# io3.net
KiCad netlist of a schematic drawn in EAGLE
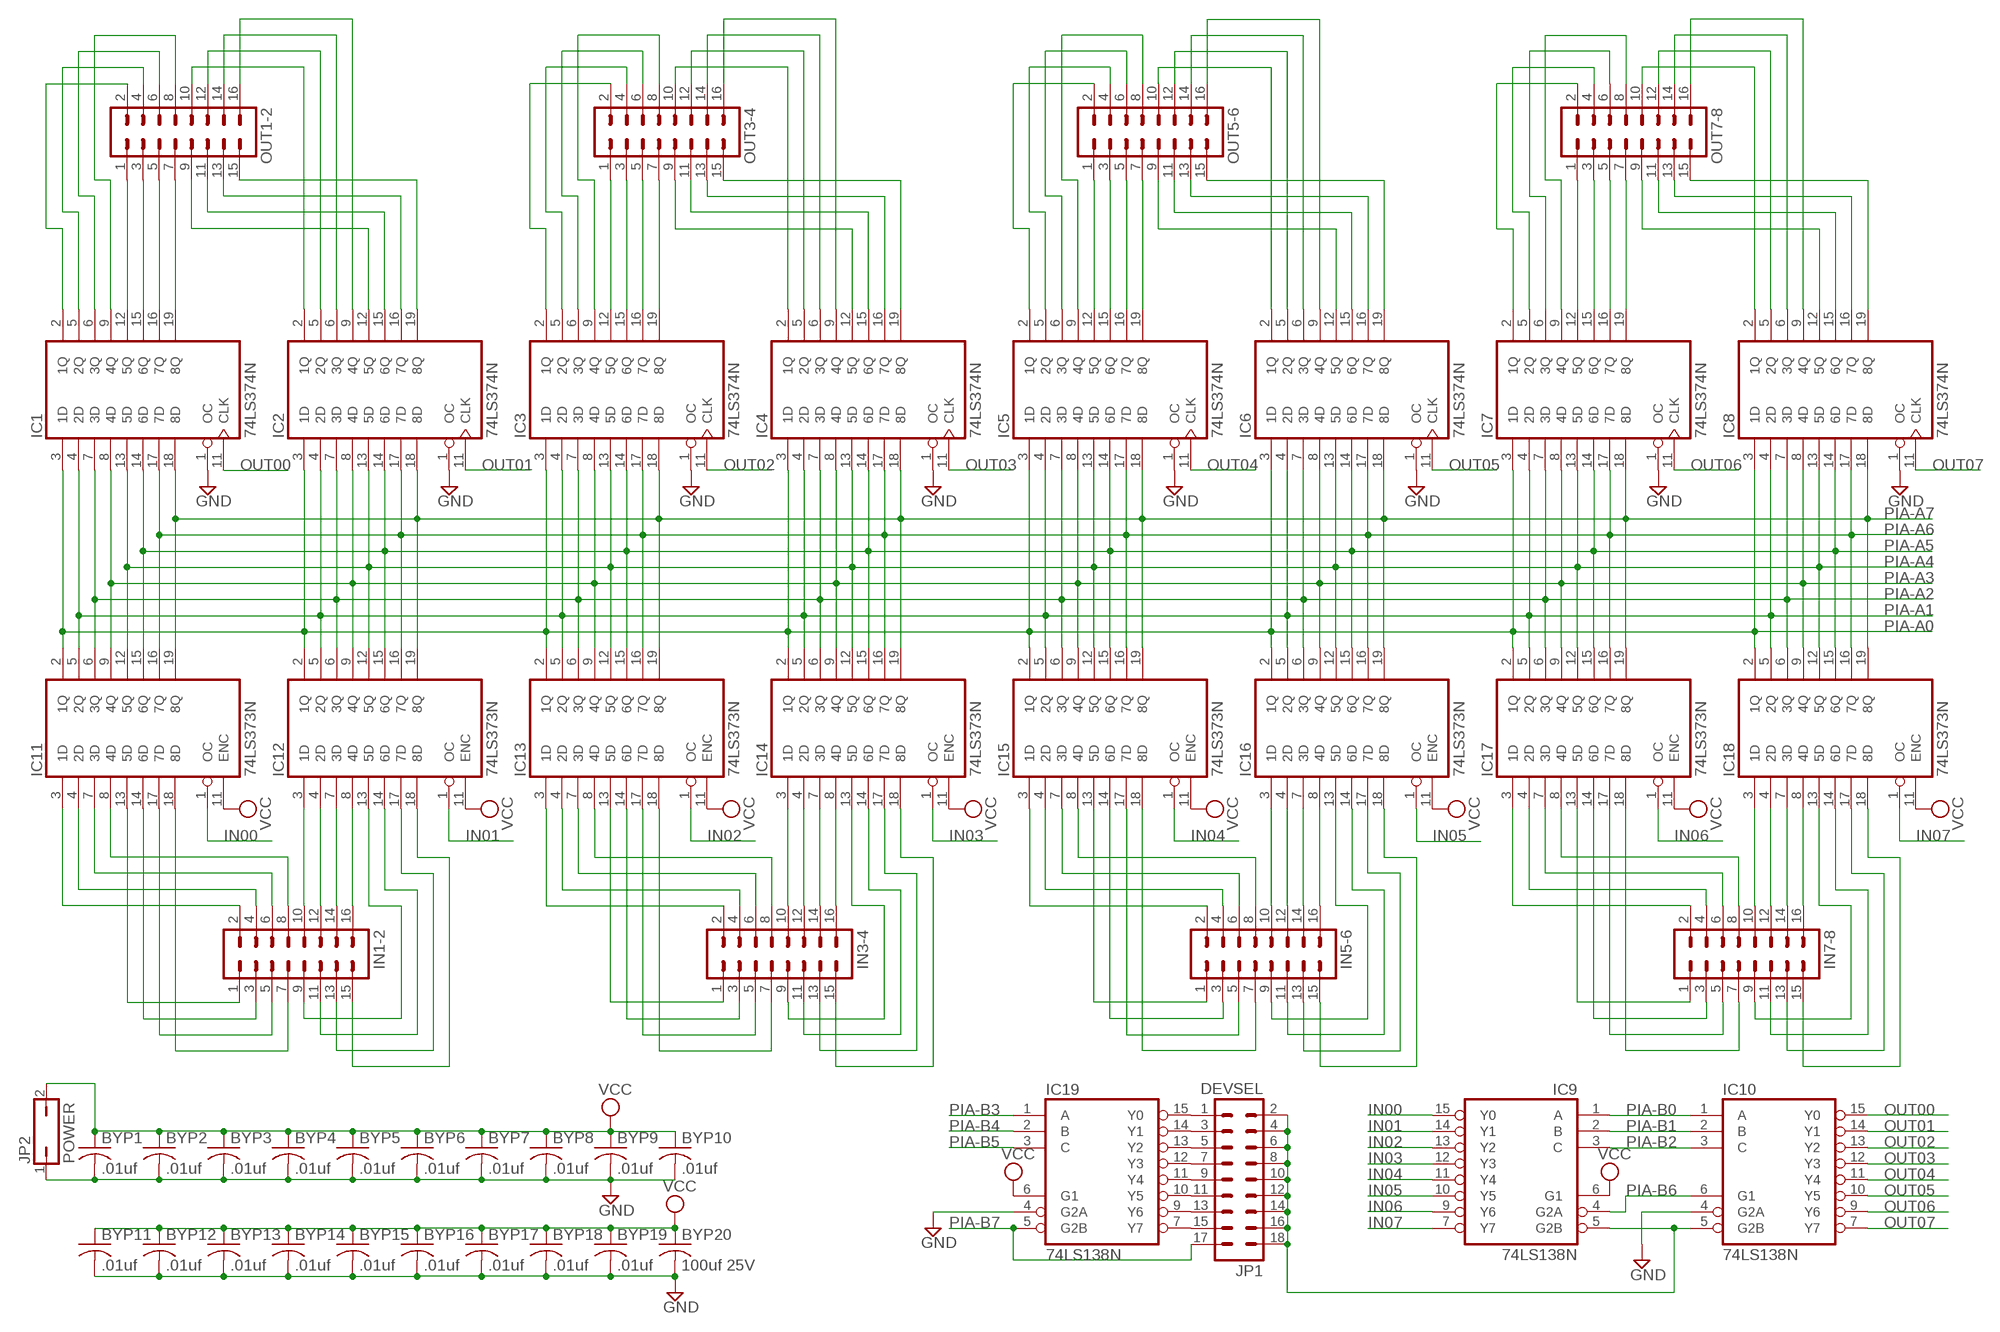
[diagram p0: schematic, sheet 1]
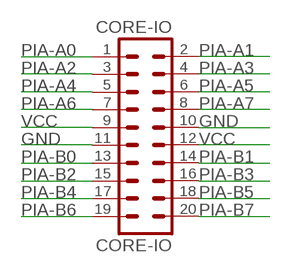
[diagram p1: schematic, sheet 2]

(export (version "E")
  (design (tool "Eeschema 10.0.6"))
  (components
    (comp (ref "CORE-IO")
      (value "CORE-IO")
      (footprint "eagle-import:MA10-2")
      (libsource (lib "eagle-import") (part "MA10-2"))
    )
    (comp (ref "BYP1")
      (value ".01uf")
      (footprint "eagle-import:C050-025X075")
      (libsource (lib "eagle-import") (part "C-US050-025X075"))
    )
    (comp (ref "BYP2")
      (value ".01uf")
      (footprint "eagle-import:C050-025X075")
      (libsource (lib "eagle-import") (part "C-US050-025X075"))
    )
    (comp (ref "BYP3")
      (value ".01uf")
      (footprint "eagle-import:C050-025X075")
      (libsource (lib "eagle-import") (part "C-US050-025X075"))
    )
    (comp (ref "BYP4")
      (value ".01uf")
      (footprint "eagle-import:C050-025X075")
      (libsource (lib "eagle-import") (part "C-US050-025X075"))
    )
    (comp (ref "BYP5")
      (value ".01uf")
      (footprint "eagle-import:C050-025X075")
      (libsource (lib "eagle-import") (part "C-US050-025X075"))
    )
    (comp (ref "BYP6")
      (value ".01uf")
      (footprint "eagle-import:C050-025X075")
      (libsource (lib "eagle-import") (part "C-US050-025X075"))
    )
    (comp (ref "BYP7")
      (value ".01uf")
      (footprint "eagle-import:C050-025X075")
      (libsource (lib "eagle-import") (part "C-US050-025X075"))
    )
    (comp (ref "BYP8")
      (value ".01uf")
      (footprint "eagle-import:C050-025X075")
      (libsource (lib "eagle-import") (part "C-US050-025X075"))
    )
    (comp (ref "BYP9")
      (value ".01uf")
      (footprint "eagle-import:C050-025X075")
      (libsource (lib "eagle-import") (part "C-US050-025X075"))
    )
    (comp (ref "BYP10")
      (value ".01uf")
      (footprint "eagle-import:C050-025X075")
      (libsource (lib "eagle-import") (part "C-US050-025X075"))
    )
    (comp (ref "BYP11")
      (value ".01uf")
      (footprint "eagle-import:C050-025X075")
      (libsource (lib "eagle-import") (part "C-US050-025X075"))
    )
    (comp (ref "BYP12")
      (value ".01uf")
      (footprint "eagle-import:C050-025X075")
      (libsource (lib "eagle-import") (part "C-US050-025X075"))
    )
    (comp (ref "BYP13")
      (value ".01uf")
      (footprint "eagle-import:C050-025X075")
      (libsource (lib "eagle-import") (part "C-US050-025X075"))
    )
    (comp (ref "BYP14")
      (value ".01uf")
      (footprint "eagle-import:C050-025X075")
      (libsource (lib "eagle-import") (part "C-US050-025X075"))
    )
    (comp (ref "BYP15")
      (value ".01uf")
      (footprint "eagle-import:C050-025X075")
      (libsource (lib "eagle-import") (part "C-US050-025X075"))
    )
    (comp (ref "BYP16")
      (value ".01uf")
      (footprint "eagle-import:C050-025X075")
      (libsource (lib "eagle-import") (part "C-US050-025X075"))
    )
    (comp (ref "BYP17")
      (value ".01uf")
      (footprint "eagle-import:C050-025X075")
      (libsource (lib "eagle-import") (part "C-US050-025X075"))
    )
    (comp (ref "BYP18")
      (value ".01uf")
      (footprint "eagle-import:C050-025X075")
      (libsource (lib "eagle-import") (part "C-US050-025X075"))
    )
    (comp (ref "BYP19")
      (value ".01uf")
      (footprint "eagle-import:C050-025X075")
      (libsource (lib "eagle-import") (part "C-US050-025X075"))
    )
    (comp (ref "BYP20")
      (value "100uf 25V")
      (footprint "eagle-import:C150-064X183")
      (libsource (lib "eagle-import") (part "C-US150-064X183"))
    )
    (comp (ref "IC1")
      (value "74LS374N")
      (footprint "eagle-import:DIL20")
      (libsource (lib "eagle-import") (part "74374NLS"))
    )
    (comp (ref "IC2")
      (value "74LS374N")
      (footprint "eagle-import:DIL20")
      (libsource (lib "eagle-import") (part "74374NLS"))
    )
    (comp (ref "IC3")
      (value "74LS374N")
      (footprint "eagle-import:DIL20")
      (libsource (lib "eagle-import") (part "74374NLS"))
    )
    (comp (ref "IC4")
      (value "74LS374N")
      (footprint "eagle-import:DIL20")
      (libsource (lib "eagle-import") (part "74374NLS"))
    )
    (comp (ref "IC5")
      (value "74LS374N")
      (footprint "eagle-import:DIL20")
      (libsource (lib "eagle-import") (part "74374NLS"))
    )
    (comp (ref "IC6")
      (value "74LS374N")
      (footprint "eagle-import:DIL20")
      (libsource (lib "eagle-import") (part "74374NLS"))
    )
    (comp (ref "IC7")
      (value "74LS374N")
      (footprint "eagle-import:DIL20")
      (libsource (lib "eagle-import") (part "74374NLS"))
    )
    (comp (ref "IC8")
      (value "74LS374N")
      (footprint "eagle-import:DIL20")
      (libsource (lib "eagle-import") (part "74374NLS"))
    )
    (comp (ref "IC9")
      (value "74LS138N")
      (footprint "eagle-import:DIL16")
      (libsource (lib "eagle-import") (part "74138NLS"))
    )
    (comp (ref "IC10")
      (value "74LS138N")
      (footprint "eagle-import:DIL16")
      (libsource (lib "eagle-import") (part "74138NLS"))
    )
    (comp (ref "IC11")
      (value "74LS373N")
      (footprint "eagle-import:DIL20")
      (libsource (lib "eagle-import") (part "74373NLS"))
    )
    (comp (ref "IC12")
      (value "74LS373N")
      (footprint "eagle-import:DIL20")
      (libsource (lib "eagle-import") (part "74373NLS"))
    )
    (comp (ref "IC13")
      (value "74LS373N")
      (footprint "eagle-import:DIL20")
      (libsource (lib "eagle-import") (part "74373NLS"))
    )
    (comp (ref "IC14")
      (value "74LS373N")
      (footprint "eagle-import:DIL20")
      (libsource (lib "eagle-import") (part "74373NLS"))
    )
    (comp (ref "IC15")
      (value "74LS373N")
      (footprint "eagle-import:DIL20")
      (libsource (lib "eagle-import") (part "74373NLS"))
    )
    (comp (ref "IC16")
      (value "74LS373N")
      (footprint "eagle-import:DIL20")
      (libsource (lib "eagle-import") (part "74373NLS"))
    )
    (comp (ref "IC17")
      (value "74LS373N")
      (footprint "eagle-import:DIL20")
      (libsource (lib "eagle-import") (part "74373NLS"))
    )
    (comp (ref "IC18")
      (value "74LS373N")
      (footprint "eagle-import:DIL20")
      (libsource (lib "eagle-import") (part "74373NLS"))
    )
    (comp (ref "IC19")
      (value "74LS138N")
      (footprint "eagle-import:DIL16")
      (libsource (lib "eagle-import") (part "74138NLS"))
    )
    (comp (ref "IN1-2")
      (value "MA08-2")
      (footprint "eagle-import:MA08-2")
      (libsource (lib "eagle-import") (part "MA08-2"))
    )
    (comp (ref "IN3-4")
      (value "MA08-2")
      (footprint "eagle-import:MA08-2")
      (libsource (lib "eagle-import") (part "MA08-2"))
    )
    (comp (ref "IN5-6")
      (value "MA08-2")
      (footprint "eagle-import:MA08-2")
      (libsource (lib "eagle-import") (part "MA08-2"))
    )
    (comp (ref "IN7-8")
      (value "MA08-2")
      (footprint "eagle-import:MA08-2")
      (libsource (lib "eagle-import") (part "MA08-2"))
    )
    (comp (ref "JP1")
      (value "DEVSEL")
      (footprint "eagle-import:MA09-2")
      (libsource (lib "eagle-import") (part "MA09-2"))
    )
    (comp (ref "JP2")
      (value "POWER")
      (footprint "eagle-import:JP1")
      (libsource (lib "eagle-import") (part "JP1Q"))
    )
    (comp (ref "OUT1-2")
      (value "MA08-2")
      (footprint "eagle-import:MA08-2")
      (libsource (lib "eagle-import") (part "MA08-2"))
    )
    (comp (ref "OUT3-4")
      (value "MA08-2")
      (footprint "eagle-import:MA08-2")
      (libsource (lib "eagle-import") (part "MA08-2"))
    )
    (comp (ref "OUT5-6")
      (value "MA08-2")
      (footprint "eagle-import:MA08-2")
      (libsource (lib "eagle-import") (part "MA08-2"))
    )
    (comp (ref "OUT7-8")
      (value "MA08-2")
      (footprint "eagle-import:MA08-2")
      (libsource (lib "eagle-import") (part "MA08-2"))
    )
  )
  (nets
    (net (code "1") (name "GND") (class "Default")
      (node (ref "BYP1") (pin "2") (pinfunction "2_2") (pintype "passive"))
      (node (ref "BYP10") (pin "2") (pinfunction "2_2") (pintype "passive"))
      (node (ref "BYP11") (pin "2") (pinfunction "2_2") (pintype "passive"))
      (node (ref "BYP12") (pin "2") (pinfunction "2_2") (pintype "passive"))
      (node (ref "BYP13") (pin "2") (pinfunction "2_2") (pintype "passive"))
      (node (ref "BYP14") (pin "2") (pinfunction "2_2") (pintype "passive"))
      (node (ref "BYP15") (pin "2") (pinfunction "2_2") (pintype "passive"))
      (node (ref "BYP16") (pin "2") (pinfunction "2_2") (pintype "passive"))
      (node (ref "BYP17") (pin "2") (pinfunction "2_2") (pintype "passive"))
      (node (ref "BYP18") (pin "2") (pinfunction "2_2") (pintype "passive"))
      (node (ref "BYP19") (pin "2") (pinfunction "2_2") (pintype "passive"))
      (node (ref "BYP2") (pin "2") (pinfunction "2_2") (pintype "passive"))
      (node (ref "BYP20") (pin "2") (pinfunction "2_2") (pintype "passive"))
      (node (ref "BYP3") (pin "2") (pinfunction "2_2") (pintype "passive"))
      (node (ref "BYP4") (pin "2") (pinfunction "2_2") (pintype "passive"))
      (node (ref "BYP5") (pin "2") (pinfunction "2_2") (pintype "passive"))
      (node (ref "BYP6") (pin "2") (pinfunction "2_2") (pintype "passive"))
      (node (ref "BYP7") (pin "2") (pinfunction "2_2") (pintype "passive"))
      (node (ref "BYP8") (pin "2") (pinfunction "2_2") (pintype "passive"))
      (node (ref "BYP9") (pin "2") (pinfunction "2_2") (pintype "passive"))
      (node (ref "CORE-IO") (pin "10") (pinfunction "10_10") (pintype "passive"))
      (node (ref "CORE-IO") (pin "11") (pinfunction "11_11") (pintype "passive"))
      (node (ref "IC1") (pin "1") (pinfunction "OC_1") (pintype "input"))
      (node (ref "IC10") (pin "4") (pinfunction "G2A_4") (pintype "input"))
      (node (ref "IC19") (pin "4") (pinfunction "G2A_4") (pintype "input"))
      (node (ref "IC2") (pin "1") (pinfunction "OC_1") (pintype "input"))
      (node (ref "IC3") (pin "1") (pinfunction "OC_1") (pintype "input"))
      (node (ref "IC4") (pin "1") (pinfunction "OC_1") (pintype "input"))
      (node (ref "IC5") (pin "1") (pinfunction "OC_1") (pintype "input"))
      (node (ref "IC6") (pin "1") (pinfunction "OC_1") (pintype "input"))
      (node (ref "IC7") (pin "1") (pinfunction "OC_1") (pintype "input"))
      (node (ref "IC8") (pin "1") (pinfunction "OC_1") (pintype "input"))
      (node (ref "JP2") (pin "1") (pinfunction "1_1") (pintype "passive"))
    )
    (net (code "2") (name "IN00") (class "Default")
      (node (ref "IC11") (pin "1") (pinfunction "OC_1") (pintype "input"))
      (node (ref "IC9") (pin "15") (pinfunction "Y0_15") (pintype "output"))
    )
    (net (code "3") (name "IN01") (class "Default")
      (node (ref "IC12") (pin "1") (pinfunction "OC_1") (pintype "input"))
      (node (ref "IC9") (pin "14") (pinfunction "Y1_14") (pintype "output"))
    )
    (net (code "4") (name "IN02") (class "Default")
      (node (ref "IC13") (pin "1") (pinfunction "OC_1") (pintype "input"))
      (node (ref "IC9") (pin "13") (pinfunction "Y2_13") (pintype "output"))
    )
    (net (code "5") (name "IN03") (class "Default")
      (node (ref "IC14") (pin "1") (pinfunction "OC_1") (pintype "input"))
      (node (ref "IC9") (pin "12") (pinfunction "Y3_12") (pintype "output"))
    )
    (net (code "6") (name "IN04") (class "Default")
      (node (ref "IC15") (pin "1") (pinfunction "OC_1") (pintype "input"))
      (node (ref "IC9") (pin "11") (pinfunction "Y4_11") (pintype "output"))
    )
    (net (code "7") (name "IN05") (class "Default")
      (node (ref "IC16") (pin "1") (pinfunction "OC_1") (pintype "input"))
      (node (ref "IC9") (pin "10") (pinfunction "Y5_10") (pintype "output"))
    )
    (net (code "8") (name "IN06") (class "Default")
      (node (ref "IC17") (pin "1") (pinfunction "OC_1") (pintype "input"))
      (node (ref "IC9") (pin "9") (pinfunction "Y6_9") (pintype "output"))
    )
    (net (code "9") (name "IN07") (class "Default")
      (node (ref "IC18") (pin "1") (pinfunction "OC_1") (pintype "input"))
      (node (ref "IC9") (pin "7") (pinfunction "Y7_7") (pintype "output"))
    )
    (net (code "10") (name "Net-(IC1A-1Q)") (class "Default")
      (node (ref "IC1") (pin "2") (pinfunction "1Q_2") (pintype "tri_state"))
      (node (ref "OUT1-2") (pin "2") (pinfunction "2_2") (pintype "passive"))
    )
    (net (code "11") (name "Net-(IC1A-2Q)") (class "Default")
      (node (ref "IC1") (pin "5") (pinfunction "2Q_5") (pintype "tri_state"))
      (node (ref "OUT1-2") (pin "4") (pinfunction "4_4") (pintype "passive"))
    )
    (net (code "12") (name "Net-(IC1A-3Q)") (class "Default")
      (node (ref "IC1") (pin "6") (pinfunction "3Q_6") (pintype "tri_state"))
      (node (ref "OUT1-2") (pin "6") (pinfunction "6_6") (pintype "passive"))
    )
    (net (code "13") (name "Net-(IC1A-4Q)") (class "Default")
      (node (ref "IC1") (pin "9") (pinfunction "4Q_9") (pintype "tri_state"))
      (node (ref "OUT1-2") (pin "8") (pinfunction "8_8") (pintype "passive"))
    )
    (net (code "14") (name "Net-(IC1A-5Q)") (class "Default")
      (node (ref "IC1") (pin "12") (pinfunction "5Q_12") (pintype "tri_state"))
      (node (ref "OUT1-2") (pin "1") (pinfunction "1_1") (pintype "passive"))
    )
    (net (code "15") (name "Net-(IC1A-6Q)") (class "Default")
      (node (ref "IC1") (pin "15") (pinfunction "6Q_15") (pintype "tri_state"))
      (node (ref "OUT1-2") (pin "3") (pinfunction "3_3") (pintype "passive"))
    )
    (net (code "16") (name "Net-(IC1A-7Q)") (class "Default")
      (node (ref "IC1") (pin "16") (pinfunction "7Q_16") (pintype "tri_state"))
      (node (ref "OUT1-2") (pin "5") (pinfunction "5_5") (pintype "passive"))
    )
    (net (code "17") (name "Net-(IC1A-8Q)") (class "Default")
      (node (ref "IC1") (pin "19") (pinfunction "8Q_19") (pintype "tri_state"))
      (node (ref "OUT1-2") (pin "7") (pinfunction "7_7") (pintype "passive"))
    )
    (net (code "18") (name "Net-(IC2A-1Q)") (class "Default")
      (node (ref "IC2") (pin "2") (pinfunction "1Q_2") (pintype "tri_state"))
      (node (ref "OUT1-2") (pin "10") (pinfunction "10_10") (pintype "passive"))
    )
    (net (code "19") (name "Net-(IC2A-2Q)") (class "Default")
      (node (ref "IC2") (pin "5") (pinfunction "2Q_5") (pintype "tri_state"))
      (node (ref "OUT1-2") (pin "12") (pinfunction "12_12") (pintype "passive"))
    )
    (net (code "20") (name "Net-(IC2A-3Q)") (class "Default")
      (node (ref "IC2") (pin "6") (pinfunction "3Q_6") (pintype "tri_state"))
      (node (ref "OUT1-2") (pin "14") (pinfunction "14_14") (pintype "passive"))
    )
    (net (code "21") (name "Net-(IC2A-4Q)") (class "Default")
      (node (ref "IC2") (pin "9") (pinfunction "4Q_9") (pintype "tri_state"))
      (node (ref "OUT1-2") (pin "16") (pinfunction "16_16") (pintype "passive"))
    )
    (net (code "22") (name "Net-(IC2A-5Q)") (class "Default")
      (node (ref "IC2") (pin "12") (pinfunction "5Q_12") (pintype "tri_state"))
      (node (ref "OUT1-2") (pin "9") (pinfunction "9_9") (pintype "passive"))
    )
    (net (code "23") (name "Net-(IC2A-6Q)") (class "Default")
      (node (ref "IC2") (pin "15") (pinfunction "6Q_15") (pintype "tri_state"))
      (node (ref "OUT1-2") (pin "11") (pinfunction "11_11") (pintype "passive"))
    )
    (net (code "24") (name "Net-(IC2A-7Q)") (class "Default")
      (node (ref "IC2") (pin "16") (pinfunction "7Q_16") (pintype "tri_state"))
      (node (ref "OUT1-2") (pin "13") (pinfunction "13_13") (pintype "passive"))
    )
    (net (code "25") (name "Net-(IC2A-8Q)") (class "Default")
      (node (ref "IC2") (pin "19") (pinfunction "8Q_19") (pintype "tri_state"))
      (node (ref "OUT1-2") (pin "15") (pinfunction "15_15") (pintype "passive"))
    )
    (net (code "26") (name "Net-(IC3A-1Q)") (class "Default")
      (node (ref "IC3") (pin "2") (pinfunction "1Q_2") (pintype "tri_state"))
      (node (ref "OUT3-4") (pin "2") (pinfunction "2_2") (pintype "passive"))
    )
    (net (code "27") (name "Net-(IC3A-2Q)") (class "Default")
      (node (ref "IC3") (pin "5") (pinfunction "2Q_5") (pintype "tri_state"))
      (node (ref "OUT3-4") (pin "4") (pinfunction "4_4") (pintype "passive"))
    )
    (net (code "28") (name "Net-(IC3A-3Q)") (class "Default")
      (node (ref "IC3") (pin "6") (pinfunction "3Q_6") (pintype "tri_state"))
      (node (ref "OUT3-4") (pin "6") (pinfunction "6_6") (pintype "passive"))
    )
    (net (code "29") (name "Net-(IC3A-4Q)") (class "Default")
      (node (ref "IC3") (pin "9") (pinfunction "4Q_9") (pintype "tri_state"))
      (node (ref "OUT3-4") (pin "8") (pinfunction "8_8") (pintype "passive"))
    )
    (net (code "30") (name "Net-(IC3A-5Q)") (class "Default")
      (node (ref "IC3") (pin "12") (pinfunction "5Q_12") (pintype "tri_state"))
      (node (ref "OUT3-4") (pin "1") (pinfunction "1_1") (pintype "passive"))
    )
    (net (code "31") (name "Net-(IC3A-6Q)") (class "Default")
      (node (ref "IC3") (pin "15") (pinfunction "6Q_15") (pintype "tri_state"))
      (node (ref "OUT3-4") (pin "3") (pinfunction "3_3") (pintype "passive"))
    )
    (net (code "32") (name "Net-(IC3A-7Q)") (class "Default")
      (node (ref "IC3") (pin "16") (pinfunction "7Q_16") (pintype "tri_state"))
      (node (ref "OUT3-4") (pin "5") (pinfunction "5_5") (pintype "passive"))
    )
    (net (code "33") (name "Net-(IC3A-8Q)") (class "Default")
      (node (ref "IC3") (pin "19") (pinfunction "8Q_19") (pintype "tri_state"))
      (node (ref "OUT3-4") (pin "7") (pinfunction "7_7") (pintype "passive"))
    )
    (net (code "34") (name "Net-(IC4A-1Q)") (class "Default")
      (node (ref "IC4") (pin "2") (pinfunction "1Q_2") (pintype "tri_state"))
      (node (ref "OUT3-4") (pin "10") (pinfunction "10_10") (pintype "passive"))
    )
    (net (code "35") (name "Net-(IC4A-2Q)") (class "Default")
      (node (ref "IC4") (pin "5") (pinfunction "2Q_5") (pintype "tri_state"))
      (node (ref "OUT3-4") (pin "12") (pinfunction "12_12") (pintype "passive"))
    )
    (net (code "36") (name "Net-(IC4A-3Q)") (class "Default")
      (node (ref "IC4") (pin "6") (pinfunction "3Q_6") (pintype "tri_state"))
      (node (ref "OUT3-4") (pin "14") (pinfunction "14_14") (pintype "passive"))
    )
    (net (code "37") (name "Net-(IC4A-4Q)") (class "Default")
      (node (ref "IC4") (pin "9") (pinfunction "4Q_9") (pintype "tri_state"))
      (node (ref "OUT3-4") (pin "16") (pinfunction "16_16") (pintype "passive"))
    )
    (net (code "38") (name "Net-(IC4A-5Q)") (class "Default")
      (node (ref "IC4") (pin "12") (pinfunction "5Q_12") (pintype "tri_state"))
      (node (ref "OUT3-4") (pin "9") (pinfunction "9_9") (pintype "passive"))
    )
    (net (code "39") (name "Net-(IC4A-6Q)") (class "Default")
      (node (ref "IC4") (pin "15") (pinfunction "6Q_15") (pintype "tri_state"))
      (node (ref "OUT3-4") (pin "11") (pinfunction "11_11") (pintype "passive"))
    )
    (net (code "40") (name "Net-(IC4A-7Q)") (class "Default")
      (node (ref "IC4") (pin "16") (pinfunction "7Q_16") (pintype "tri_state"))
      (node (ref "OUT3-4") (pin "13") (pinfunction "13_13") (pintype "passive"))
    )
    (net (code "41") (name "Net-(IC4A-8Q)") (class "Default")
      (node (ref "IC4") (pin "19") (pinfunction "8Q_19") (pintype "tri_state"))
      (node (ref "OUT3-4") (pin "15") (pinfunction "15_15") (pintype "passive"))
    )
    (net (code "42") (name "Net-(IC5A-1Q)") (class "Default")
      (node (ref "IC5") (pin "2") (pinfunction "1Q_2") (pintype "tri_state"))
      (node (ref "OUT5-6") (pin "2") (pinfunction "2_2") (pintype "passive"))
    )
    (net (code "43") (name "Net-(IC5A-2Q)") (class "Default")
      (node (ref "IC5") (pin "5") (pinfunction "2Q_5") (pintype "tri_state"))
      (node (ref "OUT5-6") (pin "4") (pinfunction "4_4") (pintype "passive"))
    )
    (net (code "44") (name "Net-(IC5A-3Q)") (class "Default")
      (node (ref "IC5") (pin "6") (pinfunction "3Q_6") (pintype "tri_state"))
      (node (ref "OUT5-6") (pin "6") (pinfunction "6_6") (pintype "passive"))
    )
    (net (code "45") (name "Net-(IC5A-4Q)") (class "Default")
      (node (ref "IC5") (pin "9") (pinfunction "4Q_9") (pintype "tri_state"))
      (node (ref "OUT5-6") (pin "8") (pinfunction "8_8") (pintype "passive"))
    )
    (net (code "46") (name "Net-(IC5A-5Q)") (class "Default")
      (node (ref "IC5") (pin "12") (pinfunction "5Q_12") (pintype "tri_state"))
      (node (ref "OUT5-6") (pin "1") (pinfunction "1_1") (pintype "passive"))
    )
    (net (code "47") (name "Net-(IC5A-6Q)") (class "Default")
      (node (ref "IC5") (pin "15") (pinfunction "6Q_15") (pintype "tri_state"))
      (node (ref "OUT5-6") (pin "3") (pinfunction "3_3") (pintype "passive"))
    )
    (net (code "48") (name "Net-(IC5A-7Q)") (class "Default")
      (node (ref "IC5") (pin "16") (pinfunction "7Q_16") (pintype "tri_state"))
      (node (ref "OUT5-6") (pin "5") (pinfunction "5_5") (pintype "passive"))
    )
    (net (code "49") (name "Net-(IC5A-8Q)") (class "Default")
      (node (ref "IC5") (pin "19") (pinfunction "8Q_19") (pintype "tri_state"))
      (node (ref "OUT5-6") (pin "7") (pinfunction "7_7") (pintype "passive"))
    )
    (net (code "50") (name "Net-(IC6A-1Q)") (class "Default")
      (node (ref "IC6") (pin "2") (pinfunction "1Q_2") (pintype "tri_state"))
      (node (ref "OUT5-6") (pin "10") (pinfunction "10_10") (pintype "passive"))
    )
    (net (code "51") (name "Net-(IC6A-2Q)") (class "Default")
      (node (ref "IC6") (pin "5") (pinfunction "2Q_5") (pintype "tri_state"))
      (node (ref "OUT5-6") (pin "12") (pinfunction "12_12") (pintype "passive"))
    )
    (net (code "52") (name "Net-(IC6A-3Q)") (class "Default")
      (node (ref "IC6") (pin "6") (pinfunction "3Q_6") (pintype "tri_state"))
      (node (ref "OUT5-6") (pin "14") (pinfunction "14_14") (pintype "passive"))
    )
    (net (code "53") (name "Net-(IC6A-4Q)") (class "Default")
      (node (ref "IC6") (pin "9") (pinfunction "4Q_9") (pintype "tri_state"))
      (node (ref "OUT5-6") (pin "16") (pinfunction "16_16") (pintype "passive"))
    )
    (net (code "54") (name "Net-(IC6A-5Q)") (class "Default")
      (node (ref "IC6") (pin "12") (pinfunction "5Q_12") (pintype "tri_state"))
      (node (ref "OUT5-6") (pin "9") (pinfunction "9_9") (pintype "passive"))
    )
    (net (code "55") (name "Net-(IC6A-6Q)") (class "Default")
      (node (ref "IC6") (pin "15") (pinfunction "6Q_15") (pintype "tri_state"))
      (node (ref "OUT5-6") (pin "11") (pinfunction "11_11") (pintype "passive"))
    )
    (net (code "56") (name "Net-(IC6A-7Q)") (class "Default")
      (node (ref "IC6") (pin "16") (pinfunction "7Q_16") (pintype "tri_state"))
      (node (ref "OUT5-6") (pin "13") (pinfunction "13_13") (pintype "passive"))
    )
    (net (code "57") (name "Net-(IC6A-8Q)") (class "Default")
      (node (ref "IC6") (pin "19") (pinfunction "8Q_19") (pintype "tri_state"))
      (node (ref "OUT5-6") (pin "15") (pinfunction "15_15") (pintype "passive"))
    )
    (net (code "58") (name "Net-(IC7A-1Q)") (class "Default")
      (node (ref "IC7") (pin "2") (pinfunction "1Q_2") (pintype "tri_state"))
      (node (ref "OUT7-8") (pin "2") (pinfunction "2_2") (pintype "passive"))
    )
    (net (code "59") (name "Net-(IC7A-2Q)") (class "Default")
      (node (ref "IC7") (pin "5") (pinfunction "2Q_5") (pintype "tri_state"))
      (node (ref "OUT7-8") (pin "4") (pinfunction "4_4") (pintype "passive"))
    )
    (net (code "60") (name "Net-(IC7A-3Q)") (class "Default")
      (node (ref "IC7") (pin "6") (pinfunction "3Q_6") (pintype "tri_state"))
      (node (ref "OUT7-8") (pin "6") (pinfunction "6_6") (pintype "passive"))
    )
    (net (code "61") (name "Net-(IC7A-4Q)") (class "Default")
      (node (ref "IC7") (pin "9") (pinfunction "4Q_9") (pintype "tri_state"))
      (node (ref "OUT7-8") (pin "8") (pinfunction "8_8") (pintype "passive"))
    )
    (net (code "62") (name "Net-(IC7A-5Q)") (class "Default")
      (node (ref "IC7") (pin "12") (pinfunction "5Q_12") (pintype "tri_state"))
      (node (ref "OUT7-8") (pin "1") (pinfunction "1_1") (pintype "passive"))
    )
    (net (code "63") (name "Net-(IC7A-6Q)") (class "Default")
      (node (ref "IC7") (pin "15") (pinfunction "6Q_15") (pintype "tri_state"))
      (node (ref "OUT7-8") (pin "3") (pinfunction "3_3") (pintype "passive"))
    )
    (net (code "64") (name "Net-(IC7A-7Q)") (class "Default")
      (node (ref "IC7") (pin "16") (pinfunction "7Q_16") (pintype "tri_state"))
      (node (ref "OUT7-8") (pin "5") (pinfunction "5_5") (pintype "passive"))
    )
    (net (code "65") (name "Net-(IC7A-8Q)") (class "Default")
      (node (ref "IC7") (pin "19") (pinfunction "8Q_19") (pintype "tri_state"))
      (node (ref "OUT7-8") (pin "7") (pinfunction "7_7") (pintype "passive"))
    )
    (net (code "66") (name "Net-(IC8A-1Q)") (class "Default")
      (node (ref "IC8") (pin "2") (pinfunction "1Q_2") (pintype "tri_state"))
      (node (ref "OUT7-8") (pin "10") (pinfunction "10_10") (pintype "passive"))
    )
    (net (code "67") (name "Net-(IC8A-2Q)") (class "Default")
      (node (ref "IC8") (pin "5") (pinfunction "2Q_5") (pintype "tri_state"))
      (node (ref "OUT7-8") (pin "12") (pinfunction "12_12") (pintype "passive"))
    )
    (net (code "68") (name "Net-(IC8A-3Q)") (class "Default")
      (node (ref "IC8") (pin "6") (pinfunction "3Q_6") (pintype "tri_state"))
      (node (ref "OUT7-8") (pin "14") (pinfunction "14_14") (pintype "passive"))
    )
    (net (code "69") (name "Net-(IC8A-4Q)") (class "Default")
      (node (ref "IC8") (pin "9") (pinfunction "4Q_9") (pintype "tri_state"))
      (node (ref "OUT7-8") (pin "16") (pinfunction "16_16") (pintype "passive"))
    )
    (net (code "70") (name "Net-(IC8A-5Q)") (class "Default")
      (node (ref "IC8") (pin "12") (pinfunction "5Q_12") (pintype "tri_state"))
      (node (ref "OUT7-8") (pin "9") (pinfunction "9_9") (pintype "passive"))
    )
    (net (code "71") (name "Net-(IC8A-6Q)") (class "Default")
      (node (ref "IC8") (pin "15") (pinfunction "6Q_15") (pintype "tri_state"))
      (node (ref "OUT7-8") (pin "11") (pinfunction "11_11") (pintype "passive"))
    )
    (net (code "72") (name "Net-(IC8A-7Q)") (class "Default")
      (node (ref "IC8") (pin "16") (pinfunction "7Q_16") (pintype "tri_state"))
      (node (ref "OUT7-8") (pin "13") (pinfunction "13_13") (pintype "passive"))
    )
    (net (code "73") (name "Net-(IC8A-8Q)") (class "Default")
      (node (ref "IC8") (pin "19") (pinfunction "8Q_19") (pintype "tri_state"))
      (node (ref "OUT7-8") (pin "15") (pinfunction "15_15") (pintype "passive"))
    )
    (net (code "74") (name "Net-(IC10A-G2B)") (class "Default")
      (node (ref "IC10") (pin "5") (pinfunction "G2B_5") (pintype "input"))
      (node (ref "IC9") (pin "5") (pinfunction "G2B_5") (pintype "input"))
      (node (ref "JP1") (pin "10") (pinfunction "10_10") (pintype "passive"))
      (node (ref "JP1") (pin "12") (pinfunction "12_12") (pintype "passive"))
      (node (ref "JP1") (pin "14") (pinfunction "14_14") (pintype "passive"))
      (node (ref "JP1") (pin "16") (pinfunction "16_16") (pintype "passive"))
      (node (ref "JP1") (pin "18") (pinfunction "18_18") (pintype "passive"))
      (node (ref "JP1") (pin "2") (pinfunction "2_2") (pintype "passive"))
      (node (ref "JP1") (pin "4") (pinfunction "4_4") (pintype "passive"))
      (node (ref "JP1") (pin "6") (pinfunction "6_6") (pintype "passive"))
      (node (ref "JP1") (pin "8") (pinfunction "8_8") (pintype "passive"))
    )
    (net (code "75") (name "Net-(IC11A-1D)") (class "Default")
      (node (ref "IC11") (pin "3") (pinfunction "1D_3") (pintype "input"))
      (node (ref "IN1-2") (pin "2") (pinfunction "2_2") (pintype "passive"))
    )
    (net (code "76") (name "Net-(IC11A-2D)") (class "Default")
      (node (ref "IC11") (pin "4") (pinfunction "2D_4") (pintype "input"))
      (node (ref "IN1-2") (pin "4") (pinfunction "4_4") (pintype "passive"))
    )
    (net (code "77") (name "Net-(IC11A-3D)") (class "Default")
      (node (ref "IC11") (pin "7") (pinfunction "3D_7") (pintype "input"))
      (node (ref "IN1-2") (pin "6") (pinfunction "6_6") (pintype "passive"))
    )
    (net (code "78") (name "Net-(IC11A-4D)") (class "Default")
      (node (ref "IC11") (pin "8") (pinfunction "4D_8") (pintype "input"))
      (node (ref "IN1-2") (pin "8") (pinfunction "8_8") (pintype "passive"))
    )
    (net (code "79") (name "Net-(IC11A-5D)") (class "Default")
      (node (ref "IC11") (pin "13") (pinfunction "5D_13") (pintype "input"))
      (node (ref "IN1-2") (pin "1") (pinfunction "1_1") (pintype "passive"))
    )
    (net (code "80") (name "Net-(IC11A-6D)") (class "Default")
      (node (ref "IC11") (pin "14") (pinfunction "6D_14") (pintype "input"))
      (node (ref "IN1-2") (pin "3") (pinfunction "3_3") (pintype "passive"))
    )
    (net (code "81") (name "Net-(IC11A-7D)") (class "Default")
      (node (ref "IC11") (pin "17") (pinfunction "7D_17") (pintype "input"))
      (node (ref "IN1-2") (pin "5") (pinfunction "5_5") (pintype "passive"))
    )
    (net (code "82") (name "Net-(IC11A-8D)") (class "Default")
      (node (ref "IC11") (pin "18") (pinfunction "8D_18") (pintype "input"))
      (node (ref "IN1-2") (pin "7") (pinfunction "7_7") (pintype "passive"))
    )
    (net (code "83") (name "Net-(IC12A-1D)") (class "Default")
      (node (ref "IC12") (pin "3") (pinfunction "1D_3") (pintype "input"))
      (node (ref "IN1-2") (pin "10") (pinfunction "10_10") (pintype "passive"))
    )
    (net (code "84") (name "Net-(IC12A-2D)") (class "Default")
      (node (ref "IC12") (pin "4") (pinfunction "2D_4") (pintype "input"))
      (node (ref "IN1-2") (pin "12") (pinfunction "12_12") (pintype "passive"))
    )
    (net (code "85") (name "Net-(IC12A-3D)") (class "Default")
      (node (ref "IC12") (pin "7") (pinfunction "3D_7") (pintype "input"))
      (node (ref "IN1-2") (pin "14") (pinfunction "14_14") (pintype "passive"))
    )
    (net (code "86") (name "Net-(IC12A-4D)") (class "Default")
      (node (ref "IC12") (pin "8") (pinfunction "4D_8") (pintype "input"))
      (node (ref "IN1-2") (pin "16") (pinfunction "16_16") (pintype "passive"))
    )
    (net (code "87") (name "Net-(IC12A-5D)") (class "Default")
      (node (ref "IC12") (pin "13") (pinfunction "5D_13") (pintype "input"))
      (node (ref "IN1-2") (pin "9") (pinfunction "9_9") (pintype "passive"))
    )
    (net (code "88") (name "Net-(IC12A-6D)") (class "Default")
      (node (ref "IC12") (pin "14") (pinfunction "6D_14") (pintype "input"))
      (node (ref "IN1-2") (pin "11") (pinfunction "11_11") (pintype "passive"))
    )
    (net (code "89") (name "Net-(IC12A-7D)") (class "Default")
      (node (ref "IC12") (pin "17") (pinfunction "7D_17") (pintype "input"))
      (node (ref "IN1-2") (pin "13") (pinfunction "13_13") (pintype "passive"))
    )
    (net (code "90") (name "Net-(IC12A-8D)") (class "Default")
      (node (ref "IC12") (pin "18") (pinfunction "8D_18") (pintype "input"))
      (node (ref "IN1-2") (pin "15") (pinfunction "15_15") (pintype "passive"))
    )
    (net (code "91") (name "Net-(IC13A-1D)") (class "Default")
      (node (ref "IC13") (pin "3") (pinfunction "1D_3") (pintype "input"))
      (node (ref "IN3-4") (pin "2") (pinfunction "2_2") (pintype "passive"))
    )
    (net (code "92") (name "Net-(IC13A-2D)") (class "Default")
      (node (ref "IC13") (pin "4") (pinfunction "2D_4") (pintype "input"))
      (node (ref "IN3-4") (pin "4") (pinfunction "4_4") (pintype "passive"))
    )
    (net (code "93") (name "Net-(IC13A-3D)") (class "Default")
      (node (ref "IC13") (pin "7") (pinfunction "3D_7") (pintype "input"))
      (node (ref "IN3-4") (pin "6") (pinfunction "6_6") (pintype "passive"))
    )
    (net (code "94") (name "Net-(IC13A-4D)") (class "Default")
      (node (ref "IC13") (pin "8") (pinfunction "4D_8") (pintype "input"))
      (node (ref "IN3-4") (pin "8") (pinfunction "8_8") (pintype "passive"))
    )
    (net (code "95") (name "Net-(IC13A-5D)") (class "Default")
      (node (ref "IC13") (pin "13") (pinfunction "5D_13") (pintype "input"))
      (node (ref "IN3-4") (pin "1") (pinfunction "1_1") (pintype "passive"))
    )
    (net (code "96") (name "Net-(IC13A-6D)") (class "Default")
      (node (ref "IC13") (pin "14") (pinfunction "6D_14") (pintype "input"))
      (node (ref "IN3-4") (pin "3") (pinfunction "3_3") (pintype "passive"))
    )
    (net (code "97") (name "Net-(IC13A-7D)") (class "Default")
      (node (ref "IC13") (pin "17") (pinfunction "7D_17") (pintype "input"))
      (node (ref "IN3-4") (pin "5") (pinfunction "5_5") (pintype "passive"))
    )
    (net (code "98") (name "Net-(IC13A-8D)") (class "Default")
      (node (ref "IC13") (pin "18") (pinfunction "8D_18") (pintype "input"))
      (node (ref "IN3-4") (pin "7") (pinfunction "7_7") (pintype "passive"))
    )
    (net (code "99") (name "Net-(IC14A-1D)") (class "Default")
      (node (ref "IC14") (pin "3") (pinfunction "1D_3") (pintype "input"))
      (node (ref "IN3-4") (pin "10") (pinfunction "10_10") (pintype "passive"))
    )
    (net (code "100") (name "Net-(IC14A-2D)") (class "Default")
      (node (ref "IC14") (pin "4") (pinfunction "2D_4") (pintype "input"))
      (node (ref "IN3-4") (pin "12") (pinfunction "12_12") (pintype "passive"))
    )
    (net (code "101") (name "Net-(IC14A-3D)") (class "Default")
      (node (ref "IC14") (pin "7") (pinfunction "3D_7") (pintype "input"))
      (node (ref "IN3-4") (pin "14") (pinfunction "14_14") (pintype "passive"))
    )
    (net (code "102") (name "Net-(IC14A-4D)") (class "Default")
      (node (ref "IC14") (pin "8") (pinfunction "4D_8") (pintype "input"))
      (node (ref "IN3-4") (pin "16") (pinfunction "16_16") (pintype "passive"))
    )
    (net (code "103") (name "Net-(IC14A-5D)") (class "Default")
      (node (ref "IC14") (pin "13") (pinfunction "5D_13") (pintype "input"))
      (node (ref "IN3-4") (pin "9") (pinfunction "9_9") (pintype "passive"))
    )
    (net (code "104") (name "Net-(IC14A-6D)") (class "Default")
      (node (ref "IC14") (pin "14") (pinfunction "6D_14") (pintype "input"))
      (node (ref "IN3-4") (pin "11") (pinfunction "11_11") (pintype "passive"))
    )
    (net (code "105") (name "Net-(IC14A-7D)") (class "Default")
      (node (ref "IC14") (pin "17") (pinfunction "7D_17") (pintype "input"))
      (node (ref "IN3-4") (pin "13") (pinfunction "13_13") (pintype "passive"))
    )
    (net (code "106") (name "Net-(IC14A-8D)") (class "Default")
      (node (ref "IC14") (pin "18") (pinfunction "8D_18") (pintype "input"))
      (node (ref "IN3-4") (pin "15") (pinfunction "15_15") (pintype "passive"))
    )
    (net (code "107") (name "Net-(IC15A-1D)") (class "Default")
      (node (ref "IC15") (pin "3") (pinfunction "1D_3") (pintype "input"))
      (node (ref "IN5-6") (pin "2") (pinfunction "2_2") (pintype "passive"))
    )
    (net (code "108") (name "Net-(IC15A-2D)") (class "Default")
      (node (ref "IC15") (pin "4") (pinfunction "2D_4") (pintype "input"))
      (node (ref "IN5-6") (pin "4") (pinfunction "4_4") (pintype "passive"))
    )
    (net (code "109") (name "Net-(IC15A-3D)") (class "Default")
      (node (ref "IC15") (pin "7") (pinfunction "3D_7") (pintype "input"))
      (node (ref "IN5-6") (pin "6") (pinfunction "6_6") (pintype "passive"))
    )
    (net (code "110") (name "Net-(IC15A-4D)") (class "Default")
      (node (ref "IC15") (pin "8") (pinfunction "4D_8") (pintype "input"))
      (node (ref "IN5-6") (pin "8") (pinfunction "8_8") (pintype "passive"))
    )
    (net (code "111") (name "Net-(IC15A-5D)") (class "Default")
      (node (ref "IC15") (pin "13") (pinfunction "5D_13") (pintype "input"))
      (node (ref "IN5-6") (pin "1") (pinfunction "1_1") (pintype "passive"))
    )
    (net (code "112") (name "Net-(IC15A-6D)") (class "Default")
      (node (ref "IC15") (pin "14") (pinfunction "6D_14") (pintype "input"))
      (node (ref "IN5-6") (pin "3") (pinfunction "3_3") (pintype "passive"))
    )
    (net (code "113") (name "Net-(IC15A-7D)") (class "Default")
      (node (ref "IC15") (pin "17") (pinfunction "7D_17") (pintype "input"))
      (node (ref "IN5-6") (pin "5") (pinfunction "5_5") (pintype "passive"))
    )
    (net (code "114") (name "Net-(IC15A-8D)") (class "Default")
      (node (ref "IC15") (pin "18") (pinfunction "8D_18") (pintype "input"))
      (node (ref "IN5-6") (pin "7") (pinfunction "7_7") (pintype "passive"))
    )
    (net (code "115") (name "Net-(IC16A-1D)") (class "Default")
      (node (ref "IC16") (pin "3") (pinfunction "1D_3") (pintype "input"))
      (node (ref "IN5-6") (pin "10") (pinfunction "10_10") (pintype "passive"))
    )
    (net (code "116") (name "Net-(IC16A-2D)") (class "Default")
      (node (ref "IC16") (pin "4") (pinfunction "2D_4") (pintype "input"))
      (node (ref "IN5-6") (pin "12") (pinfunction "12_12") (pintype "passive"))
    )
    (net (code "117") (name "Net-(IC16A-3D)") (class "Default")
      (node (ref "IC16") (pin "7") (pinfunction "3D_7") (pintype "input"))
      (node (ref "IN5-6") (pin "14") (pinfunction "14_14") (pintype "passive"))
    )
    (net (code "118") (name "Net-(IC16A-4D)") (class "Default")
      (node (ref "IC16") (pin "8") (pinfunction "4D_8") (pintype "input"))
      (node (ref "IN5-6") (pin "16") (pinfunction "16_16") (pintype "passive"))
    )
    (net (code "119") (name "Net-(IC16A-5D)") (class "Default")
      (node (ref "IC16") (pin "13") (pinfunction "5D_13") (pintype "input"))
      (node (ref "IN5-6") (pin "9") (pinfunction "9_9") (pintype "passive"))
    )
    (net (code "120") (name "Net-(IC16A-6D)") (class "Default")
      (node (ref "IC16") (pin "14") (pinfunction "6D_14") (pintype "input"))
      (node (ref "IN5-6") (pin "11") (pinfunction "11_11") (pintype "passive"))
    )
    (net (code "121") (name "Net-(IC16A-7D)") (class "Default")
      (node (ref "IC16") (pin "17") (pinfunction "7D_17") (pintype "input"))
      (node (ref "IN5-6") (pin "13") (pinfunction "13_13") (pintype "passive"))
    )
    (net (code "122") (name "Net-(IC16A-8D)") (class "Default")
      (node (ref "IC16") (pin "18") (pinfunction "8D_18") (pintype "input"))
      (node (ref "IN5-6") (pin "15") (pinfunction "15_15") (pintype "passive"))
    )
    (net (code "123") (name "Net-(IC17A-1D)") (class "Default")
      (node (ref "IC17") (pin "3") (pinfunction "1D_3") (pintype "input"))
      (node (ref "IN7-8") (pin "2") (pinfunction "2_2") (pintype "passive"))
    )
    (net (code "124") (name "Net-(IC17A-2D)") (class "Default")
      (node (ref "IC17") (pin "4") (pinfunction "2D_4") (pintype "input"))
      (node (ref "IN7-8") (pin "4") (pinfunction "4_4") (pintype "passive"))
    )
    (net (code "125") (name "Net-(IC17A-3D)") (class "Default")
      (node (ref "IC17") (pin "7") (pinfunction "3D_7") (pintype "input"))
      (node (ref "IN7-8") (pin "6") (pinfunction "6_6") (pintype "passive"))
    )
    (net (code "126") (name "Net-(IC17A-4D)") (class "Default")
      (node (ref "IC17") (pin "8") (pinfunction "4D_8") (pintype "input"))
      (node (ref "IN7-8") (pin "8") (pinfunction "8_8") (pintype "passive"))
    )
    (net (code "127") (name "Net-(IC17A-5D)") (class "Default")
      (node (ref "IC17") (pin "13") (pinfunction "5D_13") (pintype "input"))
      (node (ref "IN7-8") (pin "1") (pinfunction "1_1") (pintype "passive"))
    )
    (net (code "128") (name "Net-(IC17A-6D)") (class "Default")
      (node (ref "IC17") (pin "14") (pinfunction "6D_14") (pintype "input"))
      (node (ref "IN7-8") (pin "3") (pinfunction "3_3") (pintype "passive"))
    )
    (net (code "129") (name "Net-(IC17A-7D)") (class "Default")
      (node (ref "IC17") (pin "17") (pinfunction "7D_17") (pintype "input"))
      (node (ref "IN7-8") (pin "5") (pinfunction "5_5") (pintype "passive"))
    )
    (net (code "130") (name "Net-(IC17A-8D)") (class "Default")
      (node (ref "IC17") (pin "18") (pinfunction "8D_18") (pintype "input"))
      (node (ref "IN7-8") (pin "7") (pinfunction "7_7") (pintype "passive"))
    )
    (net (code "131") (name "Net-(IC18A-1D)") (class "Default")
      (node (ref "IC18") (pin "3") (pinfunction "1D_3") (pintype "input"))
      (node (ref "IN7-8") (pin "10") (pinfunction "10_10") (pintype "passive"))
    )
    (net (code "132") (name "Net-(IC18A-2D)") (class "Default")
      (node (ref "IC18") (pin "4") (pinfunction "2D_4") (pintype "input"))
      (node (ref "IN7-8") (pin "12") (pinfunction "12_12") (pintype "passive"))
    )
    (net (code "133") (name "Net-(IC18A-3D)") (class "Default")
      (node (ref "IC18") (pin "7") (pinfunction "3D_7") (pintype "input"))
      (node (ref "IN7-8") (pin "14") (pinfunction "14_14") (pintype "passive"))
    )
    (net (code "134") (name "Net-(IC18A-4D)") (class "Default")
      (node (ref "IC18") (pin "8") (pinfunction "4D_8") (pintype "input"))
      (node (ref "IN7-8") (pin "16") (pinfunction "16_16") (pintype "passive"))
    )
    (net (code "135") (name "Net-(IC18A-5D)") (class "Default")
      (node (ref "IC18") (pin "13") (pinfunction "5D_13") (pintype "input"))
      (node (ref "IN7-8") (pin "9") (pinfunction "9_9") (pintype "passive"))
    )
    (net (code "136") (name "Net-(IC18A-6D)") (class "Default")
      (node (ref "IC18") (pin "14") (pinfunction "6D_14") (pintype "input"))
      (node (ref "IN7-8") (pin "11") (pinfunction "11_11") (pintype "passive"))
    )
    (net (code "137") (name "Net-(IC18A-7D)") (class "Default")
      (node (ref "IC18") (pin "17") (pinfunction "7D_17") (pintype "input"))
      (node (ref "IN7-8") (pin "13") (pinfunction "13_13") (pintype "passive"))
    )
    (net (code "138") (name "Net-(IC18A-8D)") (class "Default")
      (node (ref "IC18") (pin "18") (pinfunction "8D_18") (pintype "input"))
      (node (ref "IN7-8") (pin "15") (pinfunction "15_15") (pintype "passive"))
    )
    (net (code "139") (name "Net-(IC19A-Y0)") (class "Default")
      (node (ref "IC19") (pin "15") (pinfunction "Y0_15") (pintype "output"))
      (node (ref "JP1") (pin "1") (pinfunction "1_1") (pintype "passive"))
    )
    (net (code "140") (name "Net-(IC19A-Y1)") (class "Default")
      (node (ref "IC19") (pin "14") (pinfunction "Y1_14") (pintype "output"))
      (node (ref "JP1") (pin "3") (pinfunction "3_3") (pintype "passive"))
    )
    (net (code "141") (name "Net-(IC19A-Y2)") (class "Default")
      (node (ref "IC19") (pin "13") (pinfunction "Y2_13") (pintype "output"))
      (node (ref "JP1") (pin "5") (pinfunction "5_5") (pintype "passive"))
    )
    (net (code "142") (name "Net-(IC19A-Y3)") (class "Default")
      (node (ref "IC19") (pin "12") (pinfunction "Y3_12") (pintype "output"))
      (node (ref "JP1") (pin "7") (pinfunction "7_7") (pintype "passive"))
    )
    (net (code "143") (name "Net-(IC19A-Y4)") (class "Default")
      (node (ref "IC19") (pin "11") (pinfunction "Y4_11") (pintype "output"))
      (node (ref "JP1") (pin "9") (pinfunction "9_9") (pintype "passive"))
    )
    (net (code "144") (name "Net-(IC19A-Y5)") (class "Default")
      (node (ref "IC19") (pin "10") (pinfunction "Y5_10") (pintype "output"))
      (node (ref "JP1") (pin "11") (pinfunction "11_11") (pintype "passive"))
    )
    (net (code "145") (name "Net-(IC19A-Y6)") (class "Default")
      (node (ref "IC19") (pin "9") (pinfunction "Y6_9") (pintype "output"))
      (node (ref "JP1") (pin "13") (pinfunction "13_13") (pintype "passive"))
    )
    (net (code "146") (name "Net-(IC19A-Y7)") (class "Default")
      (node (ref "IC19") (pin "7") (pinfunction "Y7_7") (pintype "output"))
      (node (ref "JP1") (pin "15") (pinfunction "15_15") (pintype "passive"))
    )
    (net (code "147") (name "OUT00") (class "Default")
      (node (ref "IC1") (pin "11") (pinfunction "CLK_11") (pintype "input"))
      (node (ref "IC10") (pin "15") (pinfunction "Y0_15") (pintype "output"))
    )
    (net (code "148") (name "OUT01") (class "Default")
      (node (ref "IC10") (pin "14") (pinfunction "Y1_14") (pintype "output"))
      (node (ref "IC2") (pin "11") (pinfunction "CLK_11") (pintype "input"))
    )
    (net (code "149") (name "OUT02") (class "Default")
      (node (ref "IC10") (pin "13") (pinfunction "Y2_13") (pintype "output"))
      (node (ref "IC3") (pin "11") (pinfunction "CLK_11") (pintype "input"))
    )
    (net (code "150") (name "OUT03") (class "Default")
      (node (ref "IC10") (pin "12") (pinfunction "Y3_12") (pintype "output"))
      (node (ref "IC4") (pin "11") (pinfunction "CLK_11") (pintype "input"))
    )
    (net (code "151") (name "OUT04") (class "Default")
      (node (ref "IC10") (pin "11") (pinfunction "Y4_11") (pintype "output"))
      (node (ref "IC5") (pin "11") (pinfunction "CLK_11") (pintype "input"))
    )
    (net (code "152") (name "OUT05") (class "Default")
      (node (ref "IC10") (pin "10") (pinfunction "Y5_10") (pintype "output"))
      (node (ref "IC6") (pin "11") (pinfunction "CLK_11") (pintype "input"))
    )
    (net (code "153") (name "OUT06") (class "Default")
      (node (ref "IC10") (pin "9") (pinfunction "Y6_9") (pintype "output"))
      (node (ref "IC7") (pin "11") (pinfunction "CLK_11") (pintype "input"))
    )
    (net (code "154") (name "OUT07") (class "Default")
      (node (ref "IC10") (pin "7") (pinfunction "Y7_7") (pintype "output"))
      (node (ref "IC8") (pin "11") (pinfunction "CLK_11") (pintype "input"))
    )
    (net (code "155") (name "PIA-A0") (class "Default")
      (node (ref "CORE-IO") (pin "1") (pinfunction "1_1") (pintype "passive"))
      (node (ref "IC1") (pin "3") (pinfunction "1D_3") (pintype "input"))
      (node (ref "IC11") (pin "2") (pinfunction "1Q_2") (pintype "tri_state"))
      (node (ref "IC12") (pin "2") (pinfunction "1Q_2") (pintype "tri_state"))
      (node (ref "IC13") (pin "2") (pinfunction "1Q_2") (pintype "tri_state"))
      (node (ref "IC14") (pin "2") (pinfunction "1Q_2") (pintype "tri_state"))
      (node (ref "IC15") (pin "2") (pinfunction "1Q_2") (pintype "tri_state"))
      (node (ref "IC16") (pin "2") (pinfunction "1Q_2") (pintype "tri_state"))
      (node (ref "IC17") (pin "2") (pinfunction "1Q_2") (pintype "tri_state"))
      (node (ref "IC18") (pin "2") (pinfunction "1Q_2") (pintype "tri_state"))
      (node (ref "IC2") (pin "3") (pinfunction "1D_3") (pintype "input"))
      (node (ref "IC3") (pin "3") (pinfunction "1D_3") (pintype "input"))
      (node (ref "IC4") (pin "3") (pinfunction "1D_3") (pintype "input"))
      (node (ref "IC5") (pin "3") (pinfunction "1D_3") (pintype "input"))
      (node (ref "IC6") (pin "3") (pinfunction "1D_3") (pintype "input"))
      (node (ref "IC7") (pin "3") (pinfunction "1D_3") (pintype "input"))
      (node (ref "IC8") (pin "3") (pinfunction "1D_3") (pintype "input"))
    )
    (net (code "156") (name "PIA-A1") (class "Default")
      (node (ref "CORE-IO") (pin "2") (pinfunction "2_2") (pintype "passive"))
      (node (ref "IC1") (pin "4") (pinfunction "2D_4") (pintype "input"))
      (node (ref "IC11") (pin "5") (pinfunction "2Q_5") (pintype "tri_state"))
      (node (ref "IC12") (pin "5") (pinfunction "2Q_5") (pintype "tri_state"))
      (node (ref "IC13") (pin "5") (pinfunction "2Q_5") (pintype "tri_state"))
      (node (ref "IC14") (pin "5") (pinfunction "2Q_5") (pintype "tri_state"))
      (node (ref "IC15") (pin "5") (pinfunction "2Q_5") (pintype "tri_state"))
      (node (ref "IC16") (pin "5") (pinfunction "2Q_5") (pintype "tri_state"))
      (node (ref "IC17") (pin "5") (pinfunction "2Q_5") (pintype "tri_state"))
      (node (ref "IC18") (pin "5") (pinfunction "2Q_5") (pintype "tri_state"))
      (node (ref "IC2") (pin "4") (pinfunction "2D_4") (pintype "input"))
      (node (ref "IC3") (pin "4") (pinfunction "2D_4") (pintype "input"))
      (node (ref "IC4") (pin "4") (pinfunction "2D_4") (pintype "input"))
      (node (ref "IC5") (pin "4") (pinfunction "2D_4") (pintype "input"))
      (node (ref "IC6") (pin "4") (pinfunction "2D_4") (pintype "input"))
      (node (ref "IC7") (pin "4") (pinfunction "2D_4") (pintype "input"))
      (node (ref "IC8") (pin "4") (pinfunction "2D_4") (pintype "input"))
    )
    (net (code "157") (name "PIA-A2") (class "Default")
      (node (ref "CORE-IO") (pin "3") (pinfunction "3_3") (pintype "passive"))
      (node (ref "IC1") (pin "7") (pinfunction "3D_7") (pintype "input"))
      (node (ref "IC11") (pin "6") (pinfunction "3Q_6") (pintype "tri_state"))
      (node (ref "IC12") (pin "6") (pinfunction "3Q_6") (pintype "tri_state"))
      (node (ref "IC13") (pin "6") (pinfunction "3Q_6") (pintype "tri_state"))
      (node (ref "IC14") (pin "6") (pinfunction "3Q_6") (pintype "tri_state"))
      (node (ref "IC15") (pin "6") (pinfunction "3Q_6") (pintype "tri_state"))
      (node (ref "IC16") (pin "6") (pinfunction "3Q_6") (pintype "tri_state"))
      (node (ref "IC17") (pin "6") (pinfunction "3Q_6") (pintype "tri_state"))
      (node (ref "IC18") (pin "6") (pinfunction "3Q_6") (pintype "tri_state"))
      (node (ref "IC2") (pin "7") (pinfunction "3D_7") (pintype "input"))
      (node (ref "IC3") (pin "7") (pinfunction "3D_7") (pintype "input"))
      (node (ref "IC4") (pin "7") (pinfunction "3D_7") (pintype "input"))
      (node (ref "IC5") (pin "7") (pinfunction "3D_7") (pintype "input"))
      (node (ref "IC6") (pin "7") (pinfunction "3D_7") (pintype "input"))
      (node (ref "IC7") (pin "7") (pinfunction "3D_7") (pintype "input"))
      (node (ref "IC8") (pin "7") (pinfunction "3D_7") (pintype "input"))
    )
    (net (code "158") (name "PIA-A3") (class "Default")
      (node (ref "CORE-IO") (pin "4") (pinfunction "4_4") (pintype "passive"))
      (node (ref "IC1") (pin "8") (pinfunction "4D_8") (pintype "input"))
      (node (ref "IC11") (pin "9") (pinfunction "4Q_9") (pintype "tri_state"))
      (node (ref "IC12") (pin "9") (pinfunction "4Q_9") (pintype "tri_state"))
      (node (ref "IC13") (pin "9") (pinfunction "4Q_9") (pintype "tri_state"))
      (node (ref "IC14") (pin "9") (pinfunction "4Q_9") (pintype "tri_state"))
      (node (ref "IC15") (pin "9") (pinfunction "4Q_9") (pintype "tri_state"))
      (node (ref "IC16") (pin "9") (pinfunction "4Q_9") (pintype "tri_state"))
      (node (ref "IC17") (pin "9") (pinfunction "4Q_9") (pintype "tri_state"))
      (node (ref "IC18") (pin "9") (pinfunction "4Q_9") (pintype "tri_state"))
      (node (ref "IC2") (pin "8") (pinfunction "4D_8") (pintype "input"))
      (node (ref "IC3") (pin "8") (pinfunction "4D_8") (pintype "input"))
      (node (ref "IC4") (pin "8") (pinfunction "4D_8") (pintype "input"))
      (node (ref "IC5") (pin "8") (pinfunction "4D_8") (pintype "input"))
      (node (ref "IC6") (pin "8") (pinfunction "4D_8") (pintype "input"))
      (node (ref "IC7") (pin "8") (pinfunction "4D_8") (pintype "input"))
      (node (ref "IC8") (pin "8") (pinfunction "4D_8") (pintype "input"))
    )
    (net (code "159") (name "PIA-A4") (class "Default")
      (node (ref "CORE-IO") (pin "5") (pinfunction "5_5") (pintype "passive"))
      (node (ref "IC1") (pin "13") (pinfunction "5D_13") (pintype "input"))
      (node (ref "IC11") (pin "12") (pinfunction "5Q_12") (pintype "tri_state"))
      (node (ref "IC12") (pin "12") (pinfunction "5Q_12") (pintype "tri_state"))
      (node (ref "IC13") (pin "12") (pinfunction "5Q_12") (pintype "tri_state"))
      (node (ref "IC14") (pin "12") (pinfunction "5Q_12") (pintype "tri_state"))
      (node (ref "IC15") (pin "12") (pinfunction "5Q_12") (pintype "tri_state"))
      (node (ref "IC16") (pin "12") (pinfunction "5Q_12") (pintype "tri_state"))
      (node (ref "IC17") (pin "12") (pinfunction "5Q_12") (pintype "tri_state"))
      (node (ref "IC18") (pin "12") (pinfunction "5Q_12") (pintype "tri_state"))
      (node (ref "IC2") (pin "13") (pinfunction "5D_13") (pintype "input"))
      (node (ref "IC3") (pin "13") (pinfunction "5D_13") (pintype "input"))
      (node (ref "IC4") (pin "13") (pinfunction "5D_13") (pintype "input"))
      (node (ref "IC5") (pin "13") (pinfunction "5D_13") (pintype "input"))
      (node (ref "IC6") (pin "13") (pinfunction "5D_13") (pintype "input"))
      (node (ref "IC7") (pin "13") (pinfunction "5D_13") (pintype "input"))
      (node (ref "IC8") (pin "13") (pinfunction "5D_13") (pintype "input"))
    )
    (net (code "160") (name "PIA-A5") (class "Default")
      (node (ref "CORE-IO") (pin "6") (pinfunction "6_6") (pintype "passive"))
      (node (ref "IC1") (pin "14") (pinfunction "6D_14") (pintype "input"))
      (node (ref "IC11") (pin "15") (pinfunction "6Q_15") (pintype "tri_state"))
      (node (ref "IC12") (pin "15") (pinfunction "6Q_15") (pintype "tri_state"))
      (node (ref "IC13") (pin "15") (pinfunction "6Q_15") (pintype "tri_state"))
      (node (ref "IC14") (pin "15") (pinfunction "6Q_15") (pintype "tri_state"))
      (node (ref "IC15") (pin "15") (pinfunction "6Q_15") (pintype "tri_state"))
      (node (ref "IC16") (pin "15") (pinfunction "6Q_15") (pintype "tri_state"))
      (node (ref "IC17") (pin "15") (pinfunction "6Q_15") (pintype "tri_state"))
      (node (ref "IC18") (pin "15") (pinfunction "6Q_15") (pintype "tri_state"))
      (node (ref "IC2") (pin "14") (pinfunction "6D_14") (pintype "input"))
      (node (ref "IC3") (pin "14") (pinfunction "6D_14") (pintype "input"))
      (node (ref "IC4") (pin "14") (pinfunction "6D_14") (pintype "input"))
      (node (ref "IC5") (pin "14") (pinfunction "6D_14") (pintype "input"))
      (node (ref "IC6") (pin "14") (pinfunction "6D_14") (pintype "input"))
      (node (ref "IC7") (pin "14") (pinfunction "6D_14") (pintype "input"))
      (node (ref "IC8") (pin "14") (pinfunction "6D_14") (pintype "input"))
    )
    (net (code "161") (name "PIA-A6") (class "Default")
      (node (ref "CORE-IO") (pin "7") (pinfunction "7_7") (pintype "passive"))
      (node (ref "IC1") (pin "17") (pinfunction "7D_17") (pintype "input"))
      (node (ref "IC11") (pin "16") (pinfunction "7Q_16") (pintype "tri_state"))
      (node (ref "IC12") (pin "16") (pinfunction "7Q_16") (pintype "tri_state"))
      (node (ref "IC13") (pin "16") (pinfunction "7Q_16") (pintype "tri_state"))
      (node (ref "IC14") (pin "16") (pinfunction "7Q_16") (pintype "tri_state"))
      (node (ref "IC15") (pin "16") (pinfunction "7Q_16") (pintype "tri_state"))
      (node (ref "IC16") (pin "16") (pinfunction "7Q_16") (pintype "tri_state"))
      (node (ref "IC17") (pin "16") (pinfunction "7Q_16") (pintype "tri_state"))
      (node (ref "IC18") (pin "16") (pinfunction "7Q_16") (pintype "tri_state"))
      (node (ref "IC2") (pin "17") (pinfunction "7D_17") (pintype "input"))
      (node (ref "IC3") (pin "17") (pinfunction "7D_17") (pintype "input"))
      (node (ref "IC4") (pin "17") (pinfunction "7D_17") (pintype "input"))
      (node (ref "IC5") (pin "17") (pinfunction "7D_17") (pintype "input"))
      (node (ref "IC6") (pin "17") (pinfunction "7D_17") (pintype "input"))
      (node (ref "IC7") (pin "17") (pinfunction "7D_17") (pintype "input"))
      (node (ref "IC8") (pin "17") (pinfunction "7D_17") (pintype "input"))
    )
    (net (code "162") (name "PIA-A7") (class "Default")
      (node (ref "CORE-IO") (pin "8") (pinfunction "8_8") (pintype "passive"))
      (node (ref "IC1") (pin "18") (pinfunction "8D_18") (pintype "input"))
      (node (ref "IC11") (pin "19") (pinfunction "8Q_19") (pintype "tri_state"))
      (node (ref "IC12") (pin "19") (pinfunction "8Q_19") (pintype "tri_state"))
      (node (ref "IC13") (pin "19") (pinfunction "8Q_19") (pintype "tri_state"))
      (node (ref "IC14") (pin "19") (pinfunction "8Q_19") (pintype "tri_state"))
      (node (ref "IC15") (pin "19") (pinfunction "8Q_19") (pintype "tri_state"))
      (node (ref "IC16") (pin "19") (pinfunction "8Q_19") (pintype "tri_state"))
      (node (ref "IC17") (pin "19") (pinfunction "8Q_19") (pintype "tri_state"))
      (node (ref "IC18") (pin "19") (pinfunction "8Q_19") (pintype "tri_state"))
      (node (ref "IC2") (pin "18") (pinfunction "8D_18") (pintype "input"))
      (node (ref "IC3") (pin "18") (pinfunction "8D_18") (pintype "input"))
      (node (ref "IC4") (pin "18") (pinfunction "8D_18") (pintype "input"))
      (node (ref "IC5") (pin "18") (pinfunction "8D_18") (pintype "input"))
      (node (ref "IC6") (pin "18") (pinfunction "8D_18") (pintype "input"))
      (node (ref "IC7") (pin "18") (pinfunction "8D_18") (pintype "input"))
      (node (ref "IC8") (pin "18") (pinfunction "8D_18") (pintype "input"))
    )
    (net (code "163") (name "PIA-B0") (class "Default")
      (node (ref "CORE-IO") (pin "13") (pinfunction "13_13") (pintype "passive"))
      (node (ref "IC10") (pin "1") (pinfunction "A_1") (pintype "input"))
      (node (ref "IC9") (pin "1") (pinfunction "A_1") (pintype "input"))
    )
    (net (code "164") (name "PIA-B1") (class "Default")
      (node (ref "CORE-IO") (pin "14") (pinfunction "14_14") (pintype "passive"))
      (node (ref "IC10") (pin "2") (pinfunction "B_2") (pintype "input"))
      (node (ref "IC9") (pin "2") (pinfunction "B_2") (pintype "input"))
    )
    (net (code "165") (name "PIA-B2") (class "Default")
      (node (ref "CORE-IO") (pin "15") (pinfunction "15_15") (pintype "passive"))
      (node (ref "IC10") (pin "3") (pinfunction "C_3") (pintype "input"))
      (node (ref "IC9") (pin "3") (pinfunction "C_3") (pintype "input"))
    )
    (net (code "166") (name "PIA-B3") (class "Default")
      (node (ref "CORE-IO") (pin "16") (pinfunction "16_16") (pintype "passive"))
      (node (ref "IC19") (pin "1") (pinfunction "A_1") (pintype "input"))
    )
    (net (code "167") (name "PIA-B4") (class "Default")
      (node (ref "CORE-IO") (pin "17") (pinfunction "17_17") (pintype "passive"))
      (node (ref "IC19") (pin "2") (pinfunction "B_2") (pintype "input"))
    )
    (net (code "168") (name "PIA-B5") (class "Default")
      (node (ref "CORE-IO") (pin "18") (pinfunction "18_18") (pintype "passive"))
      (node (ref "IC19") (pin "3") (pinfunction "C_3") (pintype "input"))
    )
    (net (code "169") (name "PIA-B6") (class "Default")
      (node (ref "CORE-IO") (pin "19") (pinfunction "19_19") (pintype "passive"))
      (node (ref "IC10") (pin "6") (pinfunction "G1_6") (pintype "input"))
      (node (ref "IC9") (pin "4") (pinfunction "G2A_4") (pintype "input"))
    )
    (net (code "170") (name "PIA-B7") (class "Default")
      (node (ref "CORE-IO") (pin "20") (pinfunction "20_20") (pintype "passive"))
      (node (ref "IC19") (pin "5") (pinfunction "G2B_5") (pintype "input"))
      (node (ref "JP1") (pin "17") (pinfunction "17_17") (pintype "passive"))
    )
    (net (code "171") (name "VCC") (class "Default")
      (node (ref "BYP1") (pin "1") (pinfunction "1_1") (pintype "passive"))
      (node (ref "BYP10") (pin "1") (pinfunction "1_1") (pintype "passive"))
      (node (ref "BYP11") (pin "1") (pinfunction "1_1") (pintype "passive"))
      (node (ref "BYP12") (pin "1") (pinfunction "1_1") (pintype "passive"))
      (node (ref "BYP13") (pin "1") (pinfunction "1_1") (pintype "passive"))
      (node (ref "BYP14") (pin "1") (pinfunction "1_1") (pintype "passive"))
      (node (ref "BYP15") (pin "1") (pinfunction "1_1") (pintype "passive"))
      (node (ref "BYP16") (pin "1") (pinfunction "1_1") (pintype "passive"))
      (node (ref "BYP17") (pin "1") (pinfunction "1_1") (pintype "passive"))
      (node (ref "BYP18") (pin "1") (pinfunction "1_1") (pintype "passive"))
      (node (ref "BYP19") (pin "1") (pinfunction "1_1") (pintype "passive"))
      (node (ref "BYP2") (pin "1") (pinfunction "1_1") (pintype "passive"))
      (node (ref "BYP20") (pin "1") (pinfunction "1_1") (pintype "passive"))
      (node (ref "BYP3") (pin "1") (pinfunction "1_1") (pintype "passive"))
      (node (ref "BYP4") (pin "1") (pinfunction "1_1") (pintype "passive"))
      (node (ref "BYP5") (pin "1") (pinfunction "1_1") (pintype "passive"))
      (node (ref "BYP6") (pin "1") (pinfunction "1_1") (pintype "passive"))
      (node (ref "BYP7") (pin "1") (pinfunction "1_1") (pintype "passive"))
      (node (ref "BYP8") (pin "1") (pinfunction "1_1") (pintype "passive"))
      (node (ref "BYP9") (pin "1") (pinfunction "1_1") (pintype "passive"))
      (node (ref "CORE-IO") (pin "12") (pinfunction "12_12") (pintype "passive"))
      (node (ref "CORE-IO") (pin "9") (pinfunction "9_9") (pintype "passive"))
      (node (ref "IC11") (pin "11") (pinfunction "ENC_11") (pintype "input"))
      (node (ref "IC12") (pin "11") (pinfunction "ENC_11") (pintype "input"))
      (node (ref "IC13") (pin "11") (pinfunction "ENC_11") (pintype "input"))
      (node (ref "IC14") (pin "11") (pinfunction "ENC_11") (pintype "input"))
      (node (ref "IC15") (pin "11") (pinfunction "ENC_11") (pintype "input"))
      (node (ref "IC16") (pin "11") (pinfunction "ENC_11") (pintype "input"))
      (node (ref "IC17") (pin "11") (pinfunction "ENC_11") (pintype "input"))
      (node (ref "IC18") (pin "11") (pinfunction "ENC_11") (pintype "input"))
      (node (ref "IC19") (pin "6") (pinfunction "G1_6") (pintype "input"))
      (node (ref "IC9") (pin "6") (pinfunction "G1_6") (pintype "input"))
      (node (ref "JP2") (pin "2") (pinfunction "2_2") (pintype "passive"))
    )
  )
)
